# door-sensor.net
KiCad netlist of a schematic drawn in EAGLE
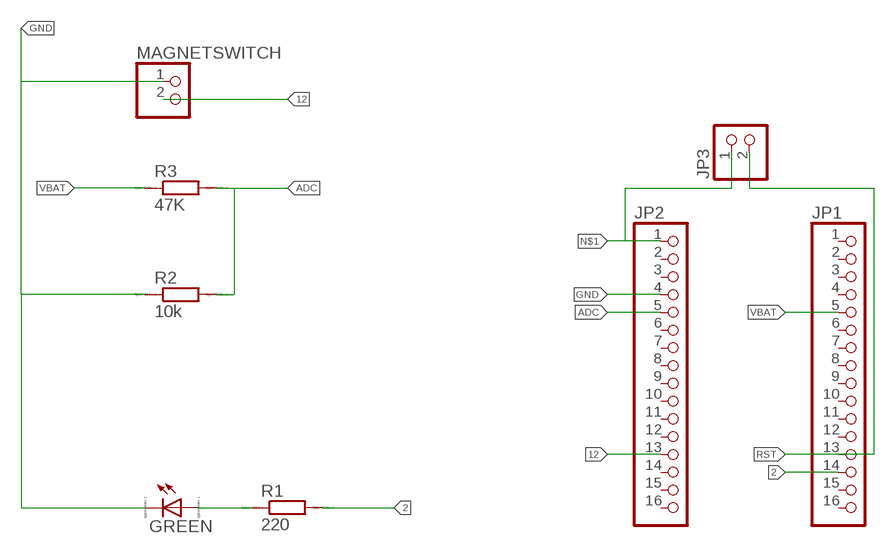
[diagram p0: schematic, sheet 1]

(export (version "E")
  (design (tool "Eeschema 10.0.6"))
  (components
    (comp (ref "GREEN")
      (value "LED_ELD260")
      (footprint "eagle-import:LED_LD260")
      (libsource (lib "eagle-import") (part "LED_ELD260"))
    )
    (comp (ref "JP1")
      (value "PINHD-1X16")
      (footprint "eagle-import:1X16")
      (libsource (lib "eagle-import") (part "PINHD-1X16"))
    )
    (comp (ref "JP2")
      (value "PINHD-1X16")
      (footprint "eagle-import:1X16")
      (libsource (lib "eagle-import") (part "PINHD-1X16"))
    )
    (comp (ref "JP3")
      (value "PINHD-1X2")
      (footprint "eagle-import:1X02")
      (libsource (lib "eagle-import") (part "PINHD-1X2"))
    )
    (comp (ref "MAGNETSWITCH")
      (value "PINHD-1X2")
      (footprint "eagle-import:1X02")
      (libsource (lib "eagle-import") (part "PINHD-1X2"))
    )
    (comp (ref "R1")
      (value "220")
      (footprint "eagle-import:0204_7")
      (libsource (lib "eagle-import") (part "R0204/7"))
    )
    (comp (ref "R2")
      (value "10k")
      (footprint "eagle-import:0204_7")
      (libsource (lib "eagle-import") (part "R0204/7"))
    )
    (comp (ref "R3")
      (value "47K")
      (footprint "eagle-import:0204_7")
      (libsource (lib "eagle-import") (part "R0204/7"))
    )
  )
  (nets
    (net (code "1") (name "2") (class "Default")
      (node (ref "JP1") (pin "14") (pinfunction "14_14") (pintype "passive"))
      (node (ref "R1") (pin "2") (pinfunction "2_2") (pintype "passive"))
    )
    (net (code "2") (name "12") (class "Default")
      (node (ref "JP2") (pin "13") (pinfunction "13_13") (pintype "passive"))
      (node (ref "MAGNETSWITCH") (pin "2") (pinfunction "2_2") (pintype "passive"))
    )
    (net (code "3") (name "ADC") (class "Default")
      (node (ref "JP2") (pin "5") (pinfunction "5_5") (pintype "passive"))
      (node (ref "R2") (pin "2") (pinfunction "2_2") (pintype "passive"))
      (node (ref "R3") (pin "2") (pinfunction "2_2") (pintype "passive"))
    )
    (net (code "4") (name "GND") (class "Default")
      (node (ref "GREEN") (pin "K") (pinfunction "C_K") (pintype "passive"))
      (node (ref "JP2") (pin "4") (pinfunction "4_4") (pintype "passive"))
      (node (ref "MAGNETSWITCH") (pin "1") (pinfunction "1_1") (pintype "passive"))
      (node (ref "R2") (pin "1") (pinfunction "1_1") (pintype "passive"))
    )
    (net (code "5") (name "N$1") (class "Default")
      (node (ref "JP2") (pin "1") (pinfunction "1_1") (pintype "passive"))
      (node (ref "JP3") (pin "1") (pinfunction "1_1") (pintype "passive"))
    )
    (net (code "6") (name "Net-(GREEN-PadA)") (class "Default")
      (node (ref "GREEN") (pin "A") (pinfunction "A_A") (pintype "passive"))
      (node (ref "R1") (pin "1") (pinfunction "1_1") (pintype "passive"))
    )
    (net (code "7") (name "RST") (class "Default")
      (node (ref "JP1") (pin "13") (pinfunction "13_13") (pintype "passive"))
      (node (ref "JP3") (pin "2") (pinfunction "2_2") (pintype "passive"))
    )
    (net (code "8") (name "VBAT") (class "Default")
      (node (ref "JP1") (pin "5") (pinfunction "5_5") (pintype "passive"))
      (node (ref "R3") (pin "1") (pinfunction "1_1") (pintype "passive"))
    )
    (net (code "9") (name "unconnected-(JP1-Pad1)") (class "Default")
      (node (ref "JP1") (pin "1") (pinfunction "1_1") (pintype "passive"))
    )
    (net (code "10") (name "unconnected-(JP1-Pad2)") (class "Default")
      (node (ref "JP1") (pin "2") (pinfunction "2_2") (pintype "passive"))
    )
    (net (code "11") (name "unconnected-(JP1-Pad3)") (class "Default")
      (node (ref "JP1") (pin "3") (pinfunction "3_3") (pintype "passive"))
    )
    (net (code "12") (name "unconnected-(JP1-Pad4)") (class "Default")
      (node (ref "JP1") (pin "4") (pinfunction "4_4") (pintype "passive"))
    )
    (net (code "13") (name "unconnected-(JP1-Pad6)") (class "Default")
      (node (ref "JP1") (pin "6") (pinfunction "6_6") (pintype "passive"))
    )
    (net (code "14") (name "unconnected-(JP1-Pad7)") (class "Default")
      (node (ref "JP1") (pin "7") (pinfunction "7_7") (pintype "passive"))
    )
    (net (code "15") (name "unconnected-(JP1-Pad8)") (class "Default")
      (node (ref "JP1") (pin "8") (pinfunction "8_8") (pintype "passive"))
    )
    (net (code "16") (name "unconnected-(JP1-Pad9)") (class "Default")
      (node (ref "JP1") (pin "9") (pinfunction "9_9") (pintype "passive"))
    )
    (net (code "17") (name "unconnected-(JP1-Pad10)") (class "Default")
      (node (ref "JP1") (pin "10") (pinfunction "10_10") (pintype "passive"))
    )
    (net (code "18") (name "unconnected-(JP1-Pad11)") (class "Default")
      (node (ref "JP1") (pin "11") (pinfunction "11_11") (pintype "passive"))
    )
    (net (code "19") (name "unconnected-(JP1-Pad12)") (class "Default")
      (node (ref "JP1") (pin "12") (pinfunction "12_12") (pintype "passive"))
    )
    (net (code "20") (name "unconnected-(JP1-Pad15)") (class "Default")
      (node (ref "JP1") (pin "15") (pinfunction "15_15") (pintype "passive"))
    )
    (net (code "21") (name "unconnected-(JP1-Pad16)") (class "Default")
      (node (ref "JP1") (pin "16") (pinfunction "16_16") (pintype "passive"))
    )
    (net (code "22") (name "unconnected-(JP2-Pad2)") (class "Default")
      (node (ref "JP2") (pin "2") (pinfunction "2_2") (pintype "passive"))
    )
    (net (code "23") (name "unconnected-(JP2-Pad3)") (class "Default")
      (node (ref "JP2") (pin "3") (pinfunction "3_3") (pintype "passive"))
    )
    (net (code "24") (name "unconnected-(JP2-Pad6)") (class "Default")
      (node (ref "JP2") (pin "6") (pinfunction "6_6") (pintype "passive"))
    )
    (net (code "25") (name "unconnected-(JP2-Pad7)") (class "Default")
      (node (ref "JP2") (pin "7") (pinfunction "7_7") (pintype "passive"))
    )
    (net (code "26") (name "unconnected-(JP2-Pad8)") (class "Default")
      (node (ref "JP2") (pin "8") (pinfunction "8_8") (pintype "passive"))
    )
    (net (code "27") (name "unconnected-(JP2-Pad9)") (class "Default")
      (node (ref "JP2") (pin "9") (pinfunction "9_9") (pintype "passive"))
    )
    (net (code "28") (name "unconnected-(JP2-Pad10)") (class "Default")
      (node (ref "JP2") (pin "10") (pinfunction "10_10") (pintype "passive"))
    )
    (net (code "29") (name "unconnected-(JP2-Pad11)") (class "Default")
      (node (ref "JP2") (pin "11") (pinfunction "11_11") (pintype "passive"))
    )
    (net (code "30") (name "unconnected-(JP2-Pad12)") (class "Default")
      (node (ref "JP2") (pin "12") (pinfunction "12_12") (pintype "passive"))
    )
    (net (code "31") (name "unconnected-(JP2-Pad14)") (class "Default")
      (node (ref "JP2") (pin "14") (pinfunction "14_14") (pintype "passive"))
    )
    (net (code "32") (name "unconnected-(JP2-Pad15)") (class "Default")
      (node (ref "JP2") (pin "15") (pinfunction "15_15") (pintype "passive"))
    )
    (net (code "33") (name "unconnected-(JP2-Pad16)") (class "Default")
      (node (ref "JP2") (pin "16") (pinfunction "16_16") (pintype "passive"))
    )
  )
)
